# Servos_Board.net
KiCad netlist of a schematic drawn in EAGLE
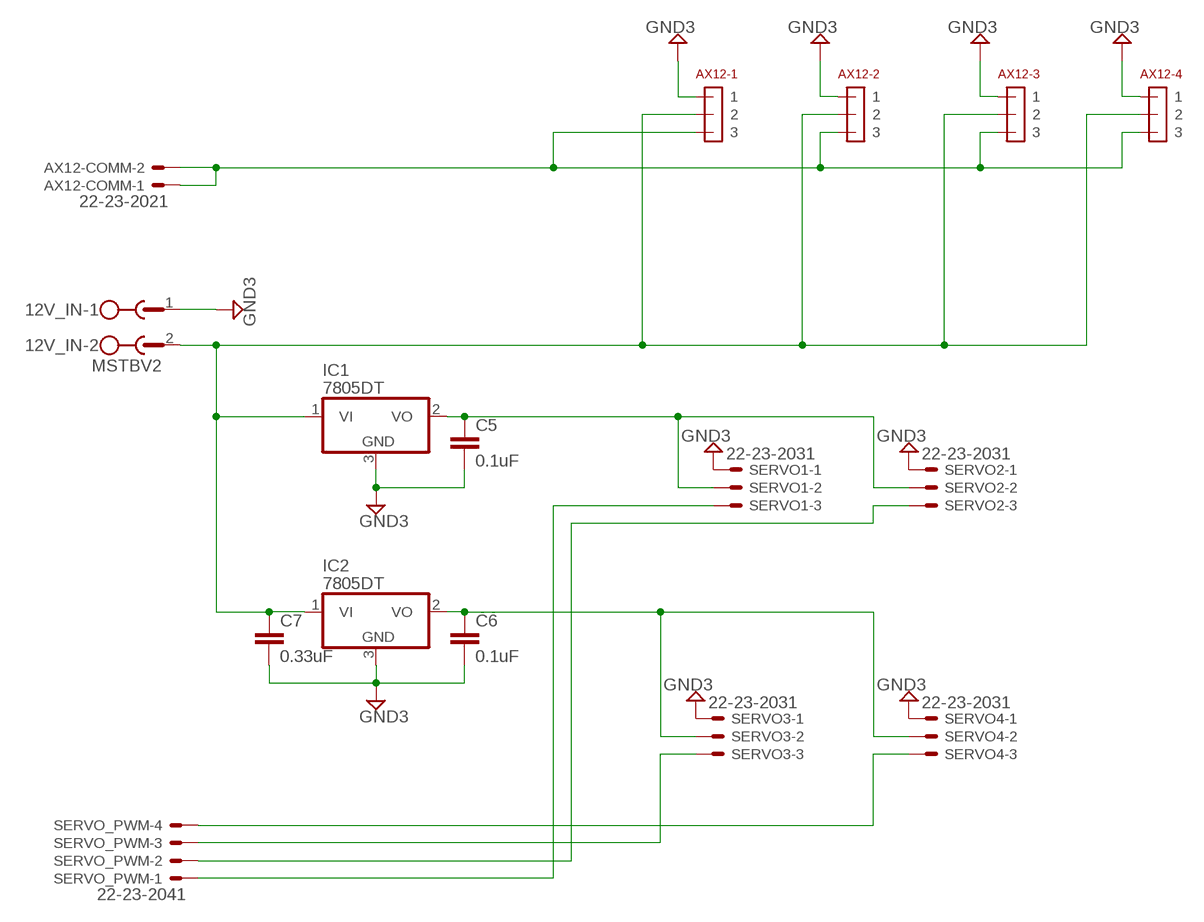
[diagram p0: schematic, sheet 1]

(export (version "E")
  (design (tool "Eeschema 10.0.6"))
  (components
    (comp (ref "12V_IN")
      (value "MSTBV2")
      (footprint "eagle-import:MSTBV2")
      (fields (field (name "MPN") "MSTBV 2,5/2-GF-5.08"))
      (libsource (lib "eagle-import") (part "MSTBV2"))
    )
    (comp (ref "AX12-1")
      (value "22-03-5035")
      (footprint "eagle-import:22-03-5035")
      (libsource (lib "eagle-import") (part "22-03-5035"))
    )
    (comp (ref "AX12-2")
      (value "22-03-5035")
      (footprint "eagle-import:22-03-5035")
      (libsource (lib "eagle-import") (part "22-03-5035"))
    )
    (comp (ref "AX12-3")
      (value "22-03-5035")
      (footprint "eagle-import:22-03-5035")
      (libsource (lib "eagle-import") (part "22-03-5035"))
    )
    (comp (ref "AX12-4")
      (value "22-03-5035")
      (footprint "eagle-import:22-03-5035")
      (libsource (lib "eagle-import") (part "22-03-5035"))
    )
    (comp (ref "AX12-COMM")
      (value "22-23-2021")
      (footprint "eagle-import:22-23-2021")
      (fields (field (name "MF") "MOLEX"))
      (libsource (lib "eagle-import") (part "22-23-2021"))
    )
    (comp (ref "C5")
      (value "0.1uF")
      (footprint "eagle-import:C0603")
      (libsource (lib "eagle-import") (part "C-EUC0603"))
    )
    (comp (ref "C6")
      (value "0.1uF")
      (footprint "eagle-import:C0603")
      (libsource (lib "eagle-import") (part "C-EUC0603"))
    )
    (comp (ref "C7")
      (value "0.33uF")
      (footprint "eagle-import:C0603")
      (libsource (lib "eagle-import") (part "C-EUC0603"))
    )
    (comp (ref "IC1")
      (value "7805DT")
      (footprint "eagle-import:TO252")
      (libsource (lib "eagle-import") (part "78DT05"))
    )
    (comp (ref "IC2")
      (value "7805DT")
      (footprint "eagle-import:TO252")
      (libsource (lib "eagle-import") (part "78DT05"))
    )
    (comp (ref "SERVO1")
      (value "22-23-2031")
      (footprint "eagle-import:22-23-2031")
      (fields (field (name "MF") "MOLEX"))
      (libsource (lib "eagle-import") (part "22-23-2031"))
    )
    (comp (ref "SERVO2")
      (value "22-23-2031")
      (footprint "eagle-import:22-23-2031")
      (fields (field (name "MF") "MOLEX"))
      (libsource (lib "eagle-import") (part "22-23-2031"))
    )
    (comp (ref "SERVO3")
      (value "22-23-2031")
      (footprint "eagle-import:22-23-2031")
      (fields (field (name "MF") "MOLEX"))
      (libsource (lib "eagle-import") (part "22-23-2031"))
    )
    (comp (ref "SERVO4")
      (value "22-23-2031")
      (footprint "eagle-import:22-23-2031")
      (fields (field (name "MF") "MOLEX"))
      (libsource (lib "eagle-import") (part "22-23-2031"))
    )
    (comp (ref "SERVO_PWM")
      (value "22-23-2041")
      (footprint "eagle-import:22-23-2041")
      (fields (field (name "MF") "MOLEX"))
      (libsource (lib "eagle-import") (part "22-23-2041"))
    )
  )
  (nets
    (net (code "1") (name "GND3") (class "Default")
      (node (ref "12V_IN") (pin "1") (pinfunction "1_1") (pintype "passive"))
      (node (ref "AX12-1") (pin "P$1") (pinfunction "1_P$1") (pintype "bidirectional"))
      (node (ref "AX12-2") (pin "P$1") (pinfunction "1_P$1") (pintype "bidirectional"))
      (node (ref "AX12-3") (pin "P$1") (pinfunction "1_P$1") (pintype "bidirectional"))
      (node (ref "AX12-4") (pin "P$1") (pinfunction "1_P$1") (pintype "bidirectional"))
      (node (ref "C5") (pin "2") (pinfunction "2_2") (pintype "passive"))
      (node (ref "C6") (pin "2") (pinfunction "2_2") (pintype "passive"))
      (node (ref "C7") (pin "2") (pinfunction "2_2") (pintype "passive"))
      (node (ref "IC1") (pin "3") (pinfunction "GND_3") (pintype "passive"))
      (node (ref "IC2") (pin "3") (pinfunction "GND_3") (pintype "passive"))
      (node (ref "SERVO1") (pin "1") (pinfunction "S_1") (pintype "passive"))
      (node (ref "SERVO2") (pin "1") (pinfunction "S_1") (pintype "passive"))
      (node (ref "SERVO3") (pin "1") (pinfunction "S_1") (pintype "passive"))
      (node (ref "SERVO4") (pin "1") (pinfunction "S_1") (pintype "passive"))
    )
    (net (code "2") (name "Net-(12V_INB-1)") (class "Default")
      (node (ref "12V_IN") (pin "2") (pinfunction "1_2") (pintype "passive"))
      (node (ref "AX12-1") (pin "P$2") (pinfunction "2_P$2") (pintype "bidirectional"))
      (node (ref "AX12-2") (pin "P$2") (pinfunction "2_P$2") (pintype "bidirectional"))
      (node (ref "AX12-3") (pin "P$2") (pinfunction "2_P$2") (pintype "bidirectional"))
      (node (ref "AX12-4") (pin "P$2") (pinfunction "2_P$2") (pintype "bidirectional"))
      (node (ref "C7") (pin "1") (pinfunction "1_1") (pintype "passive"))
      (node (ref "IC1") (pin "1") (pinfunction "VI_1") (pintype "input"))
      (node (ref "IC2") (pin "1") (pinfunction "VI_1") (pintype "input"))
    )
    (net (code "3") (name "Net-(AX12-1-3)") (class "Default")
      (node (ref "AX12-1") (pin "P$3") (pinfunction "3_P$3") (pintype "bidirectional"))
      (node (ref "AX12-2") (pin "P$3") (pinfunction "3_P$3") (pintype "bidirectional"))
      (node (ref "AX12-3") (pin "P$3") (pinfunction "3_P$3") (pintype "bidirectional"))
      (node (ref "AX12-4") (pin "P$3") (pinfunction "3_P$3") (pintype "bidirectional"))
      (node (ref "AX12-COMM") (pin "1") (pinfunction "S_1") (pintype "passive"))
      (node (ref "AX12-COMM") (pin "2") (pinfunction "S_2") (pintype "passive"))
    )
    (net (code "4") (name "Net-(IC1-VO)") (class "Default")
      (node (ref "C5") (pin "1") (pinfunction "1_1") (pintype "passive"))
      (node (ref "IC1") (pin "2") (pinfunction "VO_2") (pintype "passive"))
      (node (ref "SERVO1") (pin "2") (pinfunction "S_2") (pintype "passive"))
      (node (ref "SERVO2") (pin "2") (pinfunction "S_2") (pintype "passive"))
    )
    (net (code "5") (name "Net-(IC2-VO)") (class "Default")
      (node (ref "C6") (pin "1") (pinfunction "1_1") (pintype "passive"))
      (node (ref "IC2") (pin "2") (pinfunction "VO_2") (pintype "passive"))
      (node (ref "SERVO3") (pin "2") (pinfunction "S_2") (pintype "passive"))
      (node (ref "SERVO4") (pin "2") (pinfunction "S_2") (pintype "passive"))
    )
    (net (code "6") (name "Net-(SERVO1C-S)") (class "Default")
      (node (ref "SERVO1") (pin "3") (pinfunction "S_3") (pintype "passive"))
      (node (ref "SERVO_PWM") (pin "1") (pinfunction "S_1") (pintype "passive"))
    )
    (net (code "7") (name "Net-(SERVO2C-S)") (class "Default")
      (node (ref "SERVO2") (pin "3") (pinfunction "S_3") (pintype "passive"))
      (node (ref "SERVO_PWM") (pin "2") (pinfunction "S_2") (pintype "passive"))
    )
    (net (code "8") (name "Net-(SERVO3C-S)") (class "Default")
      (node (ref "SERVO3") (pin "3") (pinfunction "S_3") (pintype "passive"))
      (node (ref "SERVO_PWM") (pin "3") (pinfunction "S_3") (pintype "passive"))
    )
    (net (code "9") (name "Net-(SERVO4C-S)") (class "Default")
      (node (ref "SERVO4") (pin "3") (pinfunction "S_3") (pintype "passive"))
      (node (ref "SERVO_PWM") (pin "4") (pinfunction "S_4") (pintype "passive"))
    )
  )
)
